# Gripper_Control_Board.net
KiCad netlist of a schematic drawn in EAGLE
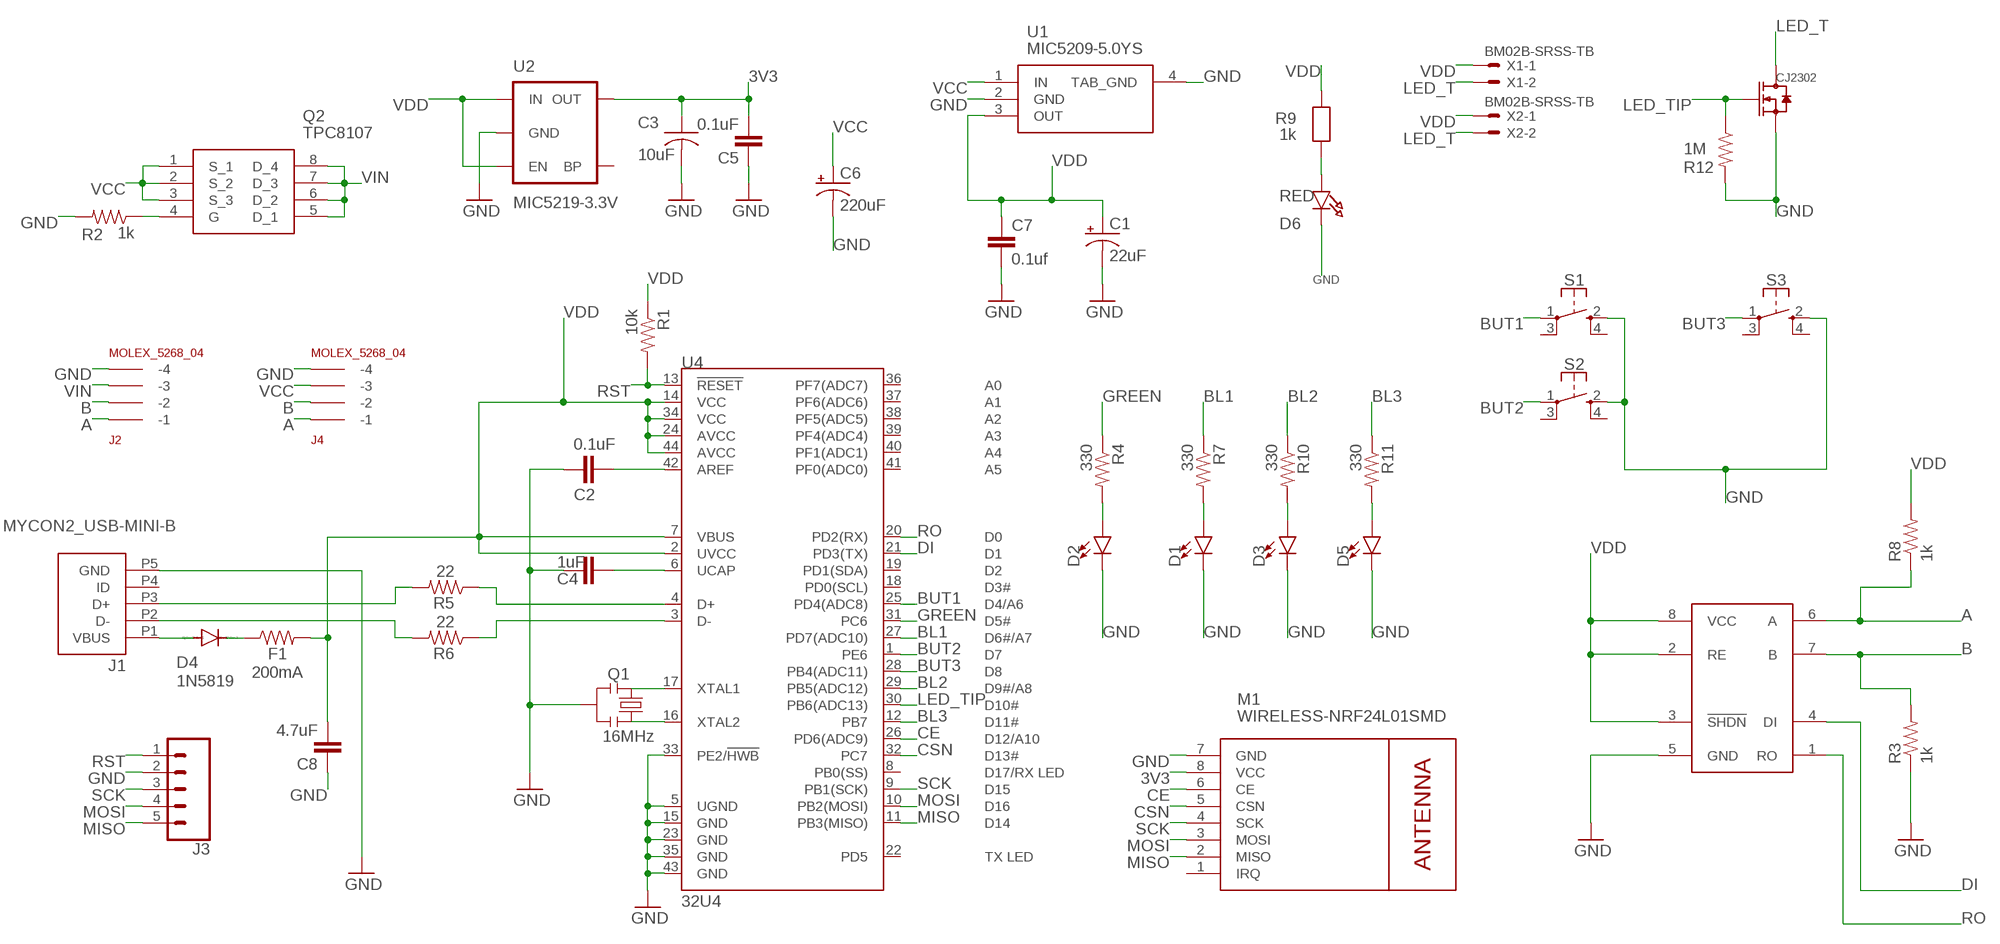
[diagram p0: schematic, sheet 1]

(export (version "E")
  (design (tool "Eeschema 10.0.6"))
  (components
    (comp (ref "C1")
      (value "22uF")
      (footprint "eagle-import:EIA3216")
      (libsource (lib "eagle-import") (part "10UF-POLAR-EIA3216-16V-10%(TANT)"))
    )
    (comp (ref "C2")
      (value "0.1uF")
      (footprint "eagle-import:0603-CAP")
      (libsource (lib "eagle-import") (part "CAP0603-CAP"))
    )
    (comp (ref "C3")
      (value "10uF")
      (footprint "eagle-import:C0805")
      (libsource (lib "eagle-import") (part "C-USC0805"))
    )
    (comp (ref "C4")
      (value "1uF")
      (footprint "eagle-import:0603-CAP")
      (libsource (lib "eagle-import") (part "CAP0603-CAP"))
    )
    (comp (ref "C5")
      (value "0.1uF")
      (footprint "eagle-import:0603-CAP")
      (libsource (lib "eagle-import") (part "CAP0603-CAP"))
    )
    (comp (ref "C6")
      (value "220uF")
      (footprint "eagle-import:PANASONIC_D")
      (libsource (lib "eagle-import") (part "100UF-POLAR-25V-20%(ELEC)"))
    )
    (comp (ref "C7")
      (value "0.1uf")
      (footprint "eagle-import:0603-CAP")
      (libsource (lib "eagle-import") (part "CAP0603-CAP"))
    )
    (comp (ref "C8")
      (value "4.7uF")
      (footprint "eagle-import:0603-CAP")
      (libsource (lib "eagle-import") (part "CAP0603-CAP"))
    )
    (comp (ref "D1")
      (value "LED0603")
      (footprint "eagle-import:LED-0603")
      (libsource (lib "eagle-import") (part "LED0603"))
    )
    (comp (ref "D2")
      (value "LED0603")
      (footprint "eagle-import:LED-0603")
      (libsource (lib "eagle-import") (part "LED0603"))
    )
    (comp (ref "D3")
      (value "LED0603")
      (footprint "eagle-import:LED-0603")
      (libsource (lib "eagle-import") (part "LED0603"))
    )
    (comp (ref "D4")
      (value "1N5819")
      (footprint "eagle-import:SOD323-W")
      (libsource (lib "eagle-import") (part "DIODE-SOD323-W"))
    )
    (comp (ref "D5")
      (value "LED0603")
      (footprint "eagle-import:LED-0603")
      (libsource (lib "eagle-import") (part "LED0603"))
    )
    (comp (ref "D6")
      (value "RED")
      (footprint "eagle-import:CHIPLED_0603")
      (libsource (lib "eagle-import") (part "microbuilder_LED0603"))
    )
    (comp (ref "F1")
      (value "200mA")
      (footprint "eagle-import:0805")
      (libsource (lib "eagle-import") (part "0.22OHM-0805-1/4W-1%"))
    )
    (comp (ref "J1")
      (value "MYCON2_USB-MINI-B")
      (footprint "eagle-import:CON2_USB_MICRO_B_AT")
      (libsource (lib "eagle-import") (part "MYCON2_USB-MINI-B"))
    )
    (comp (ref "J2")
      (value "MOLEX_5268_04")
      (footprint "eagle-import:5267-4")
      (libsource (lib "eagle-import") (part "MOLEX_5268_04"))
    )
    (comp (ref "J3")
      (value "CONN_05SMD2")
      (footprint "eagle-import:1X05_1MM_RA")
      (libsource (lib "eagle-import") (part "CONN_05SMD2"))
    )
    (comp (ref "J4")
      (value "MOLEX_5268_04")
      (footprint "eagle-import:5267-4")
      (libsource (lib "eagle-import") (part "MOLEX_5268_04"))
    )
    (comp (ref "M1")
      (value "WIRELESS-NRF24L01SMD")
      (footprint "eagle-import:WIRELESS-NRF24L01-SMD")
      (libsource (lib "eagle-import") (part "WIRELESS-NRF24L01SMD"))
    )
    (comp (ref "Q1")
      (value "16MHz")
      (footprint "eagle-import:RESONATOR-SMD")
      (libsource (lib "eagle-import") (part "RESONATORSMD"))
    )
    (comp (ref "Q2")
      (value "TPC8107")
      (footprint "eagle-import:SOIC127P600X175-8N")
      (fields
        (field (name "MANUFACTURER_PART_NUMBER") "DMG4413LSS-13")
        (field (name "MOUSER_PART_NUMBER") "621-DMG4413LSS-13")
        (field (name "RS_PART_NUMBER") "7514102P")
      )
      (libsource (lib "eagle-import") (part "TPC8107"))
    )
    (comp (ref "Q3")
      (value "CJ2302")
      (footprint "eagle-import:SOT-23")
      (libsource (lib "eagle-import") (part "SMD-MOSFET-N-CH-20V-2.1A-CJ2302(SOT-23)"))
    )
    (comp (ref "R1")
      (value "10k")
      (footprint "eagle-import:0603-RES")
      (libsource (lib "eagle-import") (part "RESISTOR0603"))
    )
    (comp (ref "R2")
      (value "1k")
      (footprint "eagle-import:0603")
      (libsource (lib "eagle-import") (part "1KOHM-0603-1/10W-1%"))
    )
    (comp (ref "R3")
      (value "1k")
      (footprint "eagle-import:0603-RES")
      (libsource (lib "eagle-import") (part "RESISTOR0603-RES"))
    )
    (comp (ref "R4")
      (value "330")
      (footprint "eagle-import:0603-RES")
      (libsource (lib "eagle-import") (part "RESISTOR0603"))
    )
    (comp (ref "R5")
      (value "22")
      (footprint "eagle-import:0603-RES")
      (fields (field (name "SPICEPREFIX") "R"))
      (libsource (lib "eagle-import") (part "RESISTOR0603"))
    )
    (comp (ref "R6")
      (value "22")
      (footprint "eagle-import:0603-RES")
      (libsource (lib "eagle-import") (part "RESISTOR0603"))
    )
    (comp (ref "R7")
      (value "330")
      (footprint "eagle-import:0603-RES")
      (fields (field (name "SPICEPREFIX") "R"))
      (libsource (lib "eagle-import") (part "RESISTOR0603"))
    )
    (comp (ref "R8")
      (value "1k")
      (footprint "eagle-import:0603-RES")
      (libsource (lib "eagle-import") (part "RESISTOR0603-RES"))
    )
    (comp (ref "R9")
      (value "1k")
      (footprint "eagle-import:0603-MINI")
      (libsource (lib "eagle-import") (part "RESISTOR0603MINI"))
    )
    (comp (ref "R10")
      (value "330")
      (footprint "eagle-import:0603-RES")
      (libsource (lib "eagle-import") (part "RESISTOR0603"))
    )
    (comp (ref "R11")
      (value "330")
      (footprint "eagle-import:0603-RES")
      (libsource (lib "eagle-import") (part "RESISTOR0603"))
    )
    (comp (ref "R12")
      (value "1M")
      (footprint "eagle-import:0603-RES")
      (fields (field (name "SPICEPREFIX") "R"))
      (libsource (lib "eagle-import") (part "RESISTOR0603"))
    )
    (comp (ref "S1")
      (value "SKSGAAE010")
      (footprint "eagle-import:SKSG")
      (fields (field (name "MOUSER_PART_NUMBER") "688-SKSGAAE010"))
      (libsource (lib "eagle-import") (part "SKSGAAE010"))
    )
    (comp (ref "S2")
      (value "SKSGAAE010")
      (footprint "eagle-import:SKSG")
      (fields (field (name "MOUSER_PART_NUMBER") "688-SKSGAAE010"))
      (libsource (lib "eagle-import") (part "SKSGAAE010"))
    )
    (comp (ref "S3")
      (value "SKSGAAE010")
      (footprint "eagle-import:SKSG")
      (fields (field (name "MOUSER_PART_NUMBER") "688-SKSGAAE010"))
      (libsource (lib "eagle-import") (part "SKSGAAE010"))
    )
    (comp (ref "U1")
      (value "MIC5209-5.0YS")
      (footprint "eagle-import:SOT230P700X180-4N")
      (fields
        (field (name "MOUSER_PART_NUMBER") "998-MIC5209-5.0YS")
        (field (name "RS_PART_NUMBER") "0453340P")
      )
      (libsource (lib "eagle-import") (part "MIC5209-5.0YS"))
    )
    (comp (ref "U2")
      (value "MIC5219-3.3V")
      (footprint "eagle-import:SOT23-5")
      (libsource (lib "eagle-import") (part "V_REG_LDOSMD"))
    )
    (comp (ref "U3")
      (value "MAX13487")
      (footprint "eagle-import:MAX13487")
      (libsource (lib "eagle-import") (part "MAX13487SOIC"))
    )
    (comp (ref "U4")
      (value "32U4")
      (footprint "eagle-import:QFN-44-NOPAD")
      (libsource (lib "eagle-import") (part "ATMEGA32U4QFN2"))
    )
    (comp (ref "X1")
      (value "BM02B-SRSS-TB")
      (footprint "eagle-import:BM02B-SRSS-TB")
      (libsource (lib "eagle-import") (part "?M02B-SRSS-TBB"))
    )
    (comp (ref "X2")
      (value "BM02B-SRSS-TB")
      (footprint "eagle-import:BM02B-SRSS-TB")
      (libsource (lib "eagle-import") (part "?M02B-SRSS-TBB"))
    )
  )
  (nets
    (net (code "1") (name "/3V3") (class "Default")
      (node (ref "C3") (pin "1") (pinfunction "1_1") (pintype "passive"))
      (node (ref "C5") (pin "2") (pinfunction "2_2") (pintype "passive"))
      (node (ref "M1") (pin "8") (pinfunction "VCC_8") (pintype "power_in"))
      (node (ref "U2") (pin "5") (pinfunction "OUT_5") (pintype "passive"))
    )
    (net (code "2") (name "/A") (class "Default")
      (node (ref "J2") (pin "P$1") (pinfunction "-1_P$1") (pintype "bidirectional"))
      (node (ref "J4") (pin "P$1") (pinfunction "-1_P$1") (pintype "bidirectional"))
      (node (ref "R8") (pin "1") (pinfunction "1_1") (pintype "passive"))
      (node (ref "U3") (pin "6") (pinfunction "A_6") (pintype "bidirectional"))
    )
    (net (code "3") (name "/B") (class "Default")
      (node (ref "J2") (pin "P$2") (pinfunction "-2_P$2") (pintype "bidirectional"))
      (node (ref "J4") (pin "P$2") (pinfunction "-2_P$2") (pintype "bidirectional"))
      (node (ref "R3") (pin "2") (pinfunction "2_2") (pintype "passive"))
      (node (ref "U3") (pin "7") (pinfunction "B_7") (pintype "bidirectional"))
    )
    (net (code "4") (name "/BL1") (class "Default")
      (node (ref "R7") (pin "1") (pinfunction "1_1") (pintype "passive"))
      (node (ref "U4") (pin "27") (pinfunction "PD7(ADC10)_27") (pintype "bidirectional"))
    )
    (net (code "5") (name "/BL2") (class "Default")
      (node (ref "R10") (pin "1") (pinfunction "1_1") (pintype "passive"))
      (node (ref "U4") (pin "29") (pinfunction "PB5(ADC12)_29") (pintype "bidirectional"))
    )
    (net (code "6") (name "/BL3") (class "Default")
      (node (ref "R11") (pin "1") (pinfunction "1_1") (pintype "passive"))
      (node (ref "U4") (pin "12") (pinfunction "PB7_12") (pintype "bidirectional"))
    )
    (net (code "7") (name "/BUT1") (class "Default")
      (node (ref "S1") (pin "1") (pinfunction "1_1") (pintype "passive"))
      (node (ref "U4") (pin "25") (pinfunction "PD4(ADC8)_25") (pintype "bidirectional"))
    )
    (net (code "8") (name "/BUT2") (class "Default")
      (node (ref "S2") (pin "1") (pinfunction "1_1") (pintype "passive"))
      (node (ref "U4") (pin "1") (pinfunction "PE6_1") (pintype "bidirectional"))
    )
    (net (code "9") (name "/BUT3") (class "Default")
      (node (ref "S3") (pin "1") (pinfunction "1_1") (pintype "passive"))
      (node (ref "U4") (pin "28") (pinfunction "PB4(ADC11)_28") (pintype "bidirectional"))
    )
    (net (code "10") (name "/CE") (class "Default")
      (node (ref "M1") (pin "6") (pinfunction "CE_6") (pintype "bidirectional"))
      (node (ref "U4") (pin "26") (pinfunction "PD6(ADC9)_26") (pintype "bidirectional"))
    )
    (net (code "11") (name "/CSN") (class "Default")
      (node (ref "M1") (pin "5") (pinfunction "CSN_5") (pintype "bidirectional"))
      (node (ref "U4") (pin "32") (pinfunction "PC7_32") (pintype "bidirectional"))
    )
    (net (code "12") (name "/DI") (class "Default")
      (node (ref "U3") (pin "4") (pinfunction "DI_4") (pintype "input"))
      (node (ref "U4") (pin "21") (pinfunction "PD3(TX)_21") (pintype "bidirectional"))
    )
    (net (code "13") (name "/GREEN") (class "Default")
      (node (ref "R4") (pin "1") (pinfunction "1_1") (pintype "passive"))
      (node (ref "U4") (pin "31") (pinfunction "PC6_31") (pintype "bidirectional"))
    )
    (net (code "14") (name "/LED_T") (class "Default")
      (node (ref "Q3") (pin "3") (pinfunction "D_3") (pintype "passive"))
      (node (ref "X1") (pin "2") (pinfunction "S_2") (pintype "passive"))
      (node (ref "X2") (pin "2") (pinfunction "S_2") (pintype "passive"))
    )
    (net (code "15") (name "/LED_TIP") (class "Default")
      (node (ref "Q3") (pin "1") (pinfunction "G_1") (pintype "passive"))
      (node (ref "R12") (pin "1") (pinfunction "1_1") (pintype "passive"))
      (node (ref "U4") (pin "30") (pinfunction "PB6(ADC13)_30") (pintype "bidirectional"))
    )
    (net (code "16") (name "/MISO") (class "Default")
      (node (ref "J3") (pin "5") (pinfunction "5_5") (pintype "passive"))
      (node (ref "M1") (pin "2") (pinfunction "MISO_2") (pintype "bidirectional"))
      (node (ref "U4") (pin "11") (pinfunction "PB3(MISO)_11") (pintype "bidirectional"))
    )
    (net (code "17") (name "/MOSI") (class "Default")
      (node (ref "J3") (pin "4") (pinfunction "4_4") (pintype "passive"))
      (node (ref "M1") (pin "3") (pinfunction "MOSI_3") (pintype "bidirectional"))
      (node (ref "U4") (pin "10") (pinfunction "PB2(MOSI)_10") (pintype "bidirectional"))
    )
    (net (code "18") (name "/RO") (class "Default")
      (node (ref "U3") (pin "1") (pinfunction "RO_1") (pintype "output"))
      (node (ref "U4") (pin "20") (pinfunction "PD2(RX)_20") (pintype "bidirectional"))
    )
    (net (code "19") (name "/RST") (class "Default")
      (node (ref "J3") (pin "1") (pinfunction "1_1") (pintype "passive"))
      (node (ref "R1") (pin "2") (pinfunction "2_2") (pintype "passive"))
      (node (ref "U4") (pin "13") (pinfunction "~{RESET}_13") (pintype "bidirectional"))
    )
    (net (code "20") (name "/SCK") (class "Default")
      (node (ref "J3") (pin "3") (pinfunction "3_3") (pintype "passive"))
      (node (ref "M1") (pin "4") (pinfunction "SCK_4") (pintype "bidirectional"))
      (node (ref "U4") (pin "9") (pinfunction "PB1(SCK)_9") (pintype "bidirectional"))
    )
    (net (code "21") (name "/VCC") (class "Default")
      (node (ref "C6") (pin "+") (pinfunction "+_+") (pintype "passive"))
      (node (ref "J4") (pin "P$3") (pinfunction "-3_P$3") (pintype "bidirectional"))
      (node (ref "Q2") (pin "1") (pinfunction "S_1_1") (pintype "bidirectional"))
      (node (ref "Q2") (pin "2") (pinfunction "S_2_2") (pintype "bidirectional"))
      (node (ref "Q2") (pin "3") (pinfunction "S_3_3") (pintype "bidirectional"))
      (node (ref "U1") (pin "1") (pinfunction "IN_1") (pintype "input"))
    )
    (net (code "22") (name "/VDD") (class "Default")
      (node (ref "C1") (pin "+") (pinfunction "+_+") (pintype "passive"))
      (node (ref "C7") (pin "1") (pinfunction "1_1") (pintype "passive"))
      (node (ref "C8") (pin "2") (pinfunction "2_2") (pintype "passive"))
      (node (ref "F1") (pin "2") (pinfunction "2_2") (pintype "passive"))
      (node (ref "R1") (pin "1") (pinfunction "1_1") (pintype "passive"))
      (node (ref "R8") (pin "2") (pinfunction "2_2") (pintype "passive"))
      (node (ref "R9") (pin "2") (pinfunction "2_2") (pintype "passive"))
      (node (ref "U1") (pin "3") (pinfunction "OUT_3") (pintype "output"))
      (node (ref "U2") (pin "1") (pinfunction "IN_1") (pintype "input"))
      (node (ref "U2") (pin "3") (pinfunction "EN_3") (pintype "input"))
      (node (ref "U3") (pin "2") (pinfunction "RE_2") (pintype "bidirectional"))
      (node (ref "U3") (pin "3") (pinfunction "~{SHDN}_3") (pintype "bidirectional"))
      (node (ref "U3") (pin "8") (pinfunction "VCC_8") (pintype "power_in"))
      (node (ref "U4") (pin "14") (pinfunction "VCC_14") (pintype "bidirectional"))
      (node (ref "U4") (pin "2") (pinfunction "UVCC_2") (pintype "bidirectional"))
      (node (ref "U4") (pin "24") (pinfunction "AVCC_24") (pintype "bidirectional"))
      (node (ref "U4") (pin "34") (pinfunction "VCC_34") (pintype "bidirectional"))
      (node (ref "U4") (pin "44") (pinfunction "AVCC_44") (pintype "bidirectional"))
      (node (ref "U4") (pin "7") (pinfunction "VBUS_7") (pintype "bidirectional"))
      (node (ref "X1") (pin "1") (pinfunction "S_1") (pintype "passive"))
      (node (ref "X2") (pin "1") (pinfunction "S_1") (pintype "passive"))
    )
    (net (code "23") (name "/VIN") (class "Default")
      (node (ref "J2") (pin "P$3") (pinfunction "-3_P$3") (pintype "bidirectional"))
      (node (ref "Q2") (pin "5") (pinfunction "D_1_5") (pintype "bidirectional"))
      (node (ref "Q2") (pin "6") (pinfunction "D_2_6") (pintype "bidirectional"))
      (node (ref "Q2") (pin "7") (pinfunction "D_3_7") (pintype "bidirectional"))
      (node (ref "Q2") (pin "8") (pinfunction "D_4_8") (pintype "bidirectional"))
    )
    (net (code "24") (name "GND") (class "Default")
      (node (ref "C1") (pin "-") (pinfunction "-_-") (pintype "passive"))
      (node (ref "C2") (pin "1") (pinfunction "1_1") (pintype "passive"))
      (node (ref "C3") (pin "2") (pinfunction "2_2") (pintype "passive"))
      (node (ref "C4") (pin "1") (pinfunction "1_1") (pintype "passive"))
      (node (ref "C5") (pin "1") (pinfunction "1_1") (pintype "passive"))
      (node (ref "C6") (pin "-") (pinfunction "-_-") (pintype "passive"))
      (node (ref "C7") (pin "2") (pinfunction "2_2") (pintype "passive"))
      (node (ref "C8") (pin "1") (pinfunction "1_1") (pintype "passive"))
      (node (ref "D1") (pin "C") (pinfunction "C_C") (pintype "passive"))
      (node (ref "D2") (pin "C") (pinfunction "C_C") (pintype "passive"))
      (node (ref "D3") (pin "C") (pinfunction "C_C") (pintype "passive"))
      (node (ref "D5") (pin "C") (pinfunction "C_C") (pintype "passive"))
      (node (ref "D6") (pin "C") (pinfunction "C_C") (pintype "passive"))
      (node (ref "J1") (pin "P5") (pinfunction "GND_P5") (pintype "passive"))
      (node (ref "J2") (pin "P$4") (pinfunction "-4_P$4") (pintype "bidirectional"))
      (node (ref "J3") (pin "2") (pinfunction "2_2") (pintype "passive"))
      (node (ref "J4") (pin "P$4") (pinfunction "-4_P$4") (pintype "bidirectional"))
      (node (ref "M1") (pin "7") (pinfunction "GND_7") (pintype "power_in"))
      (node (ref "Q1") (pin "2") (pinfunction "2_2") (pintype "passive"))
      (node (ref "Q3") (pin "2") (pinfunction "S_2") (pintype "passive"))
      (node (ref "R12") (pin "2") (pinfunction "2_2") (pintype "passive"))
      (node (ref "R2") (pin "2") (pinfunction "2_2") (pintype "passive"))
      (node (ref "R3") (pin "1") (pinfunction "1_1") (pintype "passive"))
      (node (ref "S1") (pin "2") (pinfunction "3_2") (pintype "passive"))
      (node (ref "S2") (pin "2") (pinfunction "3_2") (pintype "passive"))
      (node (ref "S3") (pin "2") (pinfunction "3_2") (pintype "passive"))
      (node (ref "U1") (pin "2") (pinfunction "GND_2") (pintype "power_in"))
      (node (ref "U1") (pin "4") (pinfunction "TAB_GND_4") (pintype "power_in"))
      (node (ref "U2") (pin "2") (pinfunction "GND_2") (pintype "input"))
      (node (ref "U3") (pin "5") (pinfunction "GND_5") (pintype "power_in"))
      (node (ref "U4") (pin "15") (pinfunction "GND_15") (pintype "bidirectional"))
      (node (ref "U4") (pin "23") (pinfunction "GND_23") (pintype "bidirectional"))
      (node (ref "U4") (pin "33") (pinfunction "PE2/~{HWB}_33") (pintype "bidirectional"))
      (node (ref "U4") (pin "35") (pinfunction "GND_35") (pintype "bidirectional"))
      (node (ref "U4") (pin "43") (pinfunction "GND_43") (pintype "bidirectional"))
      (node (ref "U4") (pin "5") (pinfunction "UGND_5") (pintype "bidirectional"))
    )
    (net (code "25") (name "Net-(D1-PadA)") (class "Default")
      (node (ref "D1") (pin "A") (pinfunction "A_A") (pintype "passive"))
      (node (ref "R7") (pin "2") (pinfunction "2_2") (pintype "passive"))
    )
    (net (code "26") (name "Net-(D2-PadA)") (class "Default")
      (node (ref "D2") (pin "A") (pinfunction "A_A") (pintype "passive"))
      (node (ref "R4") (pin "2") (pinfunction "2_2") (pintype "passive"))
    )
    (net (code "27") (name "Net-(D3-PadA)") (class "Default")
      (node (ref "D3") (pin "A") (pinfunction "A_A") (pintype "passive"))
      (node (ref "R10") (pin "2") (pinfunction "2_2") (pintype "passive"))
    )
    (net (code "28") (name "Net-(D4-PadC)") (class "Default")
      (node (ref "D4") (pin "C") (pinfunction "C_C") (pintype "passive"))
      (node (ref "F1") (pin "1") (pinfunction "1_1") (pintype "passive"))
    )
    (net (code "29") (name "Net-(D5-PadA)") (class "Default")
      (node (ref "D5") (pin "A") (pinfunction "A_A") (pintype "passive"))
      (node (ref "R11") (pin "2") (pinfunction "2_2") (pintype "passive"))
    )
    (net (code "30") (name "Net-(D6-PadA)") (class "Default")
      (node (ref "D6") (pin "A") (pinfunction "A_A") (pintype "passive"))
      (node (ref "R9") (pin "1") (pinfunction "1_1") (pintype "passive"))
    )
    (net (code "31") (name "Net-(J1-D+)") (class "Default")
      (node (ref "J1") (pin "P3") (pinfunction "D+_P3") (pintype "bidirectional"))
      (node (ref "R5") (pin "2") (pinfunction "2_2") (pintype "passive"))
    )
    (net (code "32") (name "Net-(J1-D-)") (class "Default")
      (node (ref "J1") (pin "P2") (pinfunction "D-_P2") (pintype "bidirectional"))
      (node (ref "R6") (pin "2") (pinfunction "2_2") (pintype "passive"))
    )
    (net (code "33") (name "Net-(J1-VBUS)") (class "Default")
      (node (ref "D4") (pin "A") (pinfunction "A_A") (pintype "passive"))
      (node (ref "J1") (pin "P1") (pinfunction "VBUS_P1") (pintype "power_in"))
    )
    (net (code "34") (name "Net-(Q2-G)") (class "Default")
      (node (ref "Q2") (pin "4") (pinfunction "G_4") (pintype "bidirectional"))
      (node (ref "R2") (pin "1") (pinfunction "1_1") (pintype "passive"))
    )
    (net (code "35") (name "Net-(U4-AREF)") (class "Default")
      (node (ref "C2") (pin "2") (pinfunction "2_2") (pintype "passive"))
      (node (ref "U4") (pin "42") (pinfunction "AREF_42") (pintype "bidirectional"))
    )
    (net (code "36") (name "Net-(U4-D+)") (class "Default")
      (node (ref "R5") (pin "1") (pinfunction "1_1") (pintype "passive"))
      (node (ref "U4") (pin "4") (pinfunction "D+_4") (pintype "bidirectional"))
    )
    (net (code "37") (name "Net-(U4-D-)") (class "Default")
      (node (ref "R6") (pin "1") (pinfunction "1_1") (pintype "passive"))
      (node (ref "U4") (pin "3") (pinfunction "D-_3") (pintype "bidirectional"))
    )
    (net (code "38") (name "Net-(U4-UCAP)") (class "Default")
      (node (ref "C4") (pin "2") (pinfunction "2_2") (pintype "passive"))
      (node (ref "U4") (pin "6") (pinfunction "UCAP_6") (pintype "bidirectional"))
    )
    (net (code "39") (name "Net-(U4-XTAL1)") (class "Default")
      (node (ref "Q1") (pin "1") (pinfunction "1_1") (pintype "passive"))
      (node (ref "U4") (pin "17") (pinfunction "XTAL1_17") (pintype "bidirectional"))
    )
    (net (code "40") (name "Net-(U4-XTAL2)") (class "Default")
      (node (ref "Q1") (pin "3") (pinfunction "3_3") (pintype "passive"))
      (node (ref "U4") (pin "16") (pinfunction "XTAL2_16") (pintype "bidirectional"))
    )
    (net (code "41") (name "unconnected-(J1-ID-PadP4)") (class "Default")
      (node (ref "J1") (pin "P4") (pinfunction "ID_P4") (pintype "bidirectional"))
    )
    (net (code "42") (name "unconnected-(M1-IRQ-Pad1)") (class "Default")
      (node (ref "M1") (pin "1") (pinfunction "IRQ_1") (pintype "bidirectional"))
    )
    (net (code "43") (name "unconnected-(S1-2-Pad3)") (class "Default")
      (node (ref "S1") (pin "3") (pinfunction "2_3") (pintype "passive"))
    )
    (net (code "44") (name "unconnected-(S1-Pad4)") (class "Default")
      (node (ref "S1") (pin "4") (pinfunction "4_4") (pintype "passive"))
    )
    (net (code "45") (name "unconnected-(S2-2-Pad3)") (class "Default")
      (node (ref "S2") (pin "3") (pinfunction "2_3") (pintype "passive"))
    )
    (net (code "46") (name "unconnected-(S2-Pad4)") (class "Default")
      (node (ref "S2") (pin "4") (pinfunction "4_4") (pintype "passive"))
    )
    (net (code "47") (name "unconnected-(S3-2-Pad3)") (class "Default")
      (node (ref "S3") (pin "3") (pinfunction "2_3") (pintype "passive"))
    )
    (net (code "48") (name "unconnected-(S3-Pad4)") (class "Default")
      (node (ref "S3") (pin "4") (pinfunction "4_4") (pintype "passive"))
    )
    (net (code "49") (name "unconnected-(U2-BP-Pad4)") (class "Default")
      (node (ref "U2") (pin "4") (pinfunction "BP_4") (pintype "input"))
    )
    (net (code "50") (name "unconnected-(U4-PB0(SS)-Pad8)") (class "Default")
      (node (ref "U4") (pin "8") (pinfunction "PB0(SS)_8") (pintype "bidirectional"))
    )
    (net (code "51") (name "unconnected-(U4-PD0(SCL)-Pad18)") (class "Default")
      (node (ref "U4") (pin "18") (pinfunction "PD0(SCL)_18") (pintype "bidirectional"))
    )
    (net (code "52") (name "unconnected-(U4-PD1(SDA)-Pad19)") (class "Default")
      (node (ref "U4") (pin "19") (pinfunction "PD1(SDA)_19") (pintype "bidirectional"))
    )
    (net (code "53") (name "unconnected-(U4-PD5-Pad22)") (class "Default")
      (node (ref "U4") (pin "22") (pinfunction "PD5_22") (pintype "bidirectional"))
    )
    (net (code "54") (name "unconnected-(U4-PF0(ADC0)-Pad41)") (class "Default")
      (node (ref "U4") (pin "41") (pinfunction "PF0(ADC0)_41") (pintype "bidirectional"))
    )
    (net (code "55") (name "unconnected-(U4-PF1(ADC1)-Pad40)") (class "Default")
      (node (ref "U4") (pin "40") (pinfunction "PF1(ADC1)_40") (pintype "bidirectional"))
    )
    (net (code "56") (name "unconnected-(U4-PF4(ADC4)-Pad39)") (class "Default")
      (node (ref "U4") (pin "39") (pinfunction "PF4(ADC4)_39") (pintype "bidirectional"))
    )
    (net (code "57") (name "unconnected-(U4-PF5(ADC5)-Pad38)") (class "Default")
      (node (ref "U4") (pin "38") (pinfunction "PF5(ADC5)_38") (pintype "bidirectional"))
    )
    (net (code "58") (name "unconnected-(U4-PF6(ADC6)-Pad37)") (class "Default")
      (node (ref "U4") (pin "37") (pinfunction "PF6(ADC6)_37") (pintype "bidirectional"))
    )
    (net (code "59") (name "unconnected-(U4-PF7(ADC7)-Pad36)") (class "Default")
      (node (ref "U4") (pin "36") (pinfunction "PF7(ADC7)_36") (pintype "bidirectional"))
    )
  )
)
